# I2C_Keypad.net
KiCad netlist of a schematic drawn in Altium Designer
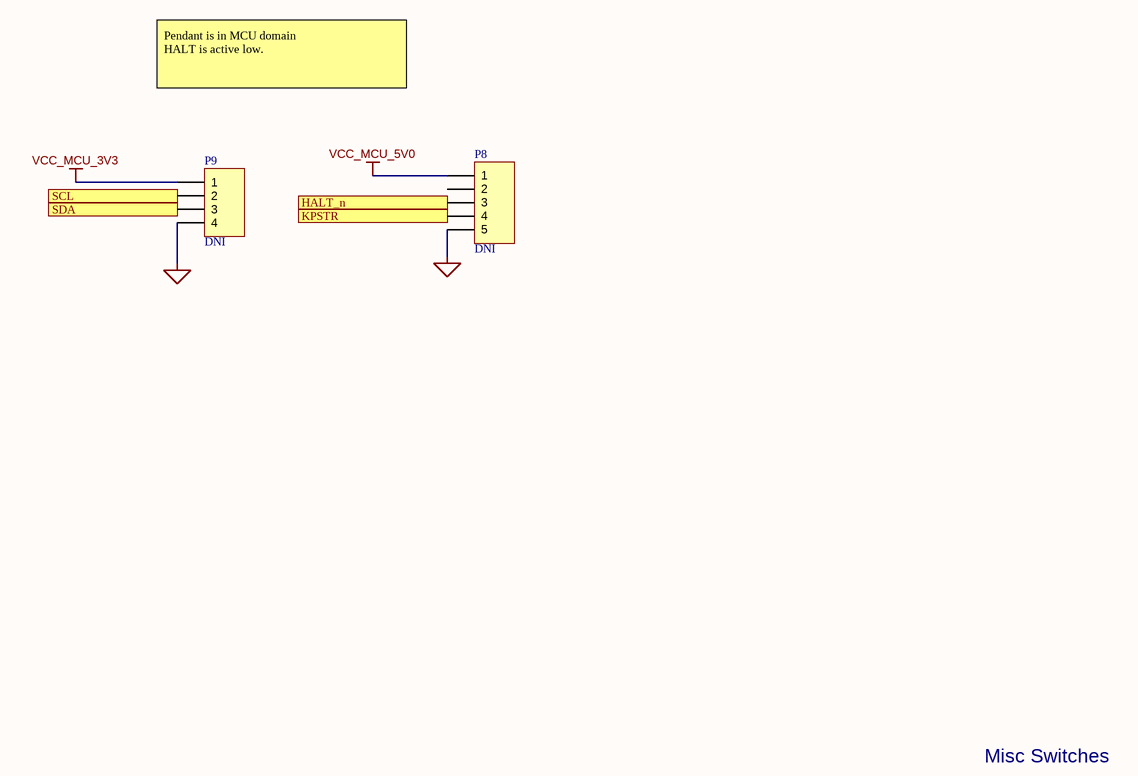
[diagram p0: I2C_Keypad.SchDoc]

(export (version "E")
  (design (tool "Eeschema 10.0.6"))
  (components
    (comp (ref "P8")
      (value "DNI")
      (footprint "HDR1X5")
      (description "Header, 5-Pin")
      (fields (field (name "PUBLISHER") "Altium Limited"))
      (libsource (lib "PrintNC_GRBLHAL_Breakout") (part "Header 5"))
    )
    (comp (ref "P9")
      (value "DNI")
      (footprint "HDR1X4")
      (description "Header, 4-Pin")
      (fields (field (name "PUBLISHER") "Altium Limited"))
      (libsource (lib "PrintNC_GRBLHAL_Breakout") (part "Header 4"))
    )
  )
  (nets
    (net (code "1") (name "/HALT_n") (class "Default")
      (node (ref "P8") (pin "3") (pinfunction "3_3") (pintype "passive"))
    )
    (net (code "2") (name "/KPSTR") (class "Default")
      (node (ref "P8") (pin "4") (pinfunction "4_4") (pintype "passive"))
    )
    (net (code "3") (name "/SCL") (class "Default")
      (node (ref "P9") (pin "2") (pinfunction "2_2") (pintype "passive"))
    )
    (net (code "4") (name "/SDA") (class "Default")
      (node (ref "P9") (pin "3") (pinfunction "3_3") (pintype "passive"))
    )
    (net (code "5") (name "MCU_GND") (class "Default")
      (node (ref "P8") (pin "5") (pinfunction "5_5") (pintype "passive"))
      (node (ref "P9") (pin "4") (pinfunction "4_4") (pintype "passive"))
    )
    (net (code "6") (name "VCC_MCU_3V3") (class "Default")
      (node (ref "P9") (pin "1") (pinfunction "1_1") (pintype "passive"))
    )
    (net (code "7") (name "VCC_MCU_5V0") (class "Default")
      (node (ref "P8") (pin "1") (pinfunction "1_1") (pintype "passive"))
    )
    (net (code "8") (name "unconnected-(P8-Pad2)") (class "Default")
      (node (ref "P8") (pin "2") (pinfunction "2_2") (pintype "passive"))
    )
  )
)
